# sonar_peripherals.net
KiCad netlist of a schematic drawn in Altium Designer
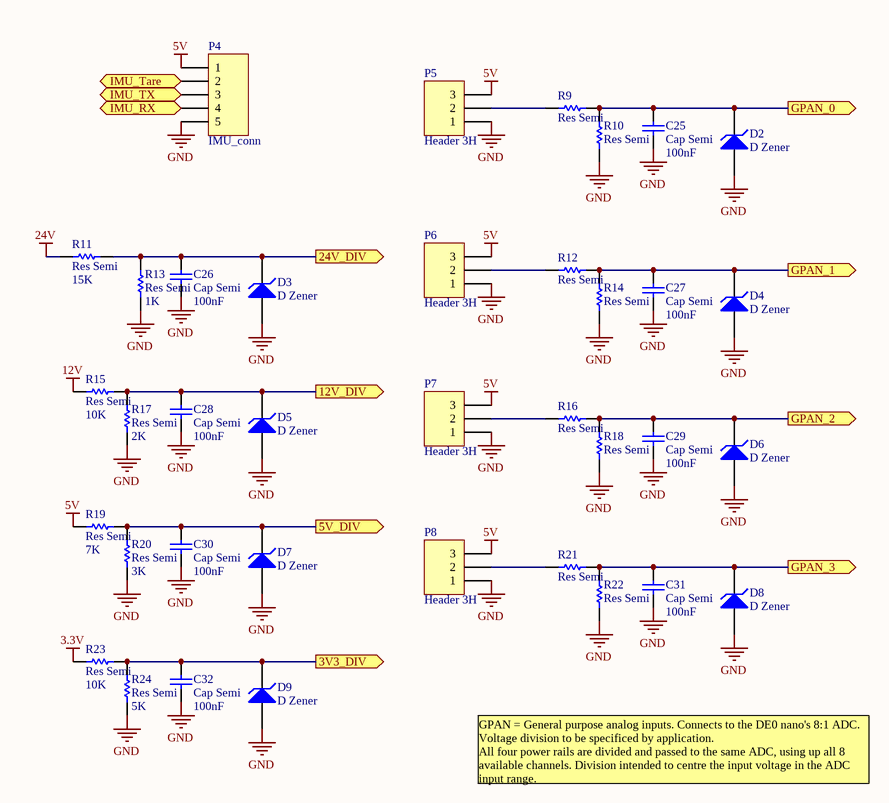
[diagram p0: sonar_peripherals.SchDoc]

(export (version "E")
  (design (tool "Eeschema 10.0.6"))
  (components
    (comp (ref "C25")
      (value "Cap Semi")
      (footprint "C0805")
      (description "Capacitor (Semiconductor SIM Model)")
      (fields (field (name "ALTIUM_VALUE") "100nF") (field (name "PUBLISHER") "Altium Limited"))
      (libsource (lib "Miscellaneous Devices") (part "Cap Semi"))
    )
    (comp (ref "C26")
      (value "Cap Semi")
      (footprint "C0805")
      (description "Capacitor (Semiconductor SIM Model)")
      (fields (field (name "ALTIUM_VALUE") "100nF") (field (name "PUBLISHER") "Altium Limited"))
      (libsource (lib "Miscellaneous Devices") (part "Cap Semi"))
    )
    (comp (ref "C27")
      (value "Cap Semi")
      (footprint "C0805")
      (description "Capacitor (Semiconductor SIM Model)")
      (fields (field (name "ALTIUM_VALUE") "100nF") (field (name "PUBLISHER") "Altium Limited"))
      (libsource (lib "Miscellaneous Devices") (part "Cap Semi"))
    )
    (comp (ref "C28")
      (value "Cap Semi")
      (footprint "C0805")
      (description "Capacitor (Semiconductor SIM Model)")
      (fields (field (name "ALTIUM_VALUE") "100nF") (field (name "PUBLISHER") "Altium Limited"))
      (libsource (lib "Miscellaneous Devices") (part "Cap Semi"))
    )
    (comp (ref "C29")
      (value "Cap Semi")
      (footprint "C0805")
      (description "Capacitor (Semiconductor SIM Model)")
      (fields (field (name "ALTIUM_VALUE") "100nF") (field (name "PUBLISHER") "Altium Limited"))
      (libsource (lib "Miscellaneous Devices") (part "Cap Semi"))
    )
    (comp (ref "C30")
      (value "Cap Semi")
      (footprint "C0805")
      (description "Capacitor (Semiconductor SIM Model)")
      (fields (field (name "ALTIUM_VALUE") "100nF") (field (name "PUBLISHER") "Altium Limited"))
      (libsource (lib "Miscellaneous Devices") (part "Cap Semi"))
    )
    (comp (ref "C31")
      (value "Cap Semi")
      (footprint "C0805")
      (description "Capacitor (Semiconductor SIM Model)")
      (fields (field (name "ALTIUM_VALUE") "100nF") (field (name "PUBLISHER") "Altium Limited"))
      (libsource (lib "Miscellaneous Devices") (part "Cap Semi"))
    )
    (comp (ref "C32")
      (value "Cap Semi")
      (footprint "C0805")
      (description "Capacitor (Semiconductor SIM Model)")
      (fields (field (name "ALTIUM_VALUE") "100nF") (field (name "PUBLISHER") "Altium Limited"))
      (libsource (lib "Miscellaneous Devices") (part "Cap Semi"))
    )
    (comp (ref "D2")
      (value "D Zener")
      (footprint "SOD-323")
      (description "Zener Diode")
      (fields (field (name "PUBLISHER") "Altium Limited"))
      (libsource (lib "Miscellaneous Devices") (part "D Zener"))
    )
    (comp (ref "D3")
      (value "D Zener")
      (footprint "SOD-323")
      (description "Zener Diode")
      (fields (field (name "PUBLISHER") "Altium Limited"))
      (libsource (lib "Miscellaneous Devices") (part "D Zener"))
    )
    (comp (ref "D4")
      (value "D Zener")
      (footprint "SOD-323")
      (description "Zener Diode")
      (fields (field (name "PUBLISHER") "Altium Limited"))
      (libsource (lib "Miscellaneous Devices") (part "D Zener"))
    )
    (comp (ref "D5")
      (value "D Zener")
      (footprint "SOD-323")
      (description "Zener Diode")
      (fields (field (name "PUBLISHER") "Altium Limited"))
      (libsource (lib "Miscellaneous Devices") (part "D Zener"))
    )
    (comp (ref "D6")
      (value "D Zener")
      (footprint "SOD-323")
      (description "Zener Diode")
      (fields (field (name "PUBLISHER") "Altium Limited"))
      (libsource (lib "Miscellaneous Devices") (part "D Zener"))
    )
    (comp (ref "D7")
      (value "D Zener")
      (footprint "SOD-323")
      (description "Zener Diode")
      (fields (field (name "PUBLISHER") "Altium Limited"))
      (libsource (lib "Miscellaneous Devices") (part "D Zener"))
    )
    (comp (ref "D8")
      (value "D Zener")
      (footprint "SOD-323")
      (description "Zener Diode")
      (fields (field (name "PUBLISHER") "Altium Limited"))
      (libsource (lib "Miscellaneous Devices") (part "D Zener"))
    )
    (comp (ref "D9")
      (value "D Zener")
      (footprint "SOD-323")
      (description "Zener Diode")
      (fields (field (name "PUBLISHER") "Altium Limited"))
      (libsource (lib "Miscellaneous Devices") (part "D Zener"))
    )
    (comp (ref "P4")
      (value "IMU_conn")
      (footprint "HDR1X5H")
      (description "Header, 5-Pin, Right Angle")
      (fields (field (name "PUBLISHER") "Altium Limited"))
      (libsource (lib "Miscellaneous Connectors") (part "Header 5H"))
    )
    (comp (ref "P5")
      (value "Header 3H")
      (footprint "HDR1X3H")
      (description "Header, 3-Pin, Right Angle")
      (fields (field (name "PUBLISHER") "Altium Limited"))
      (libsource (lib "Miscellaneous Connectors") (part "Header 3H"))
    )
    (comp (ref "P6")
      (value "Header 3H")
      (footprint "HDR1X3H")
      (description "Header, 3-Pin, Right Angle")
      (fields (field (name "PUBLISHER") "Altium Limited"))
      (libsource (lib "Miscellaneous Connectors") (part "Header 3H"))
    )
    (comp (ref "P7")
      (value "Header 3H")
      (footprint "HDR1X3H")
      (description "Header, 3-Pin, Right Angle")
      (fields (field (name "PUBLISHER") "Altium Limited"))
      (libsource (lib "Miscellaneous Connectors") (part "Header 3H"))
    )
    (comp (ref "P8")
      (value "Header 3H")
      (footprint "HDR1X3H")
      (description "Header, 3-Pin, Right Angle")
      (fields (field (name "PUBLISHER") "Altium Limited"))
      (libsource (lib "Miscellaneous Connectors") (part "Header 3H"))
    )
    (comp (ref "R9")
      (value "Res Semi")
      (footprint "6-0805_M")
      (description "Semiconductor Resistor")
      (fields (field (name "PUBLISHER") "Altium Limited"))
      (libsource (lib "Miscellaneous Devices") (part "Res Semi"))
    )
    (comp (ref "R10")
      (value "Res Semi")
      (footprint "6-0805_M")
      (description "Semiconductor Resistor")
      (fields (field (name "PUBLISHER") "Altium Limited"))
      (libsource (lib "Miscellaneous Devices") (part "Res Semi"))
    )
    (comp (ref "R11")
      (value "Res Semi")
      (footprint "6-0805_M")
      (description "Semiconductor Resistor")
      (fields (field (name "ALTIUM_VALUE") "15K") (field (name "PUBLISHER") "Altium Limited"))
      (libsource (lib "Miscellaneous Devices") (part "Res Semi"))
    )
    (comp (ref "R12")
      (value "Res Semi")
      (footprint "6-0805_M")
      (description "Semiconductor Resistor")
      (fields (field (name "PUBLISHER") "Altium Limited"))
      (libsource (lib "Miscellaneous Devices") (part "Res Semi"))
    )
    (comp (ref "R13")
      (value "Res Semi")
      (footprint "6-0805_M")
      (description "Semiconductor Resistor")
      (fields (field (name "ALTIUM_VALUE") "1K") (field (name "PUBLISHER") "Altium Limited"))
      (libsource (lib "Miscellaneous Devices") (part "Res Semi"))
    )
    (comp (ref "R14")
      (value "Res Semi")
      (footprint "6-0805_M")
      (description "Semiconductor Resistor")
      (fields (field (name "PUBLISHER") "Altium Limited"))
      (libsource (lib "Miscellaneous Devices") (part "Res Semi"))
    )
    (comp (ref "R15")
      (value "Res Semi")
      (footprint "6-0805_M")
      (description "Semiconductor Resistor")
      (fields (field (name "ALTIUM_VALUE") "10K") (field (name "PUBLISHER") "Altium Limited"))
      (libsource (lib "Miscellaneous Devices") (part "Res Semi"))
    )
    (comp (ref "R16")
      (value "Res Semi")
      (footprint "6-0805_M")
      (description "Semiconductor Resistor")
      (fields (field (name "PUBLISHER") "Altium Limited"))
      (libsource (lib "Miscellaneous Devices") (part "Res Semi"))
    )
    (comp (ref "R17")
      (value "Res Semi")
      (footprint "6-0805_M")
      (description "Semiconductor Resistor")
      (fields (field (name "ALTIUM_VALUE") "2K") (field (name "PUBLISHER") "Altium Limited"))
      (libsource (lib "Miscellaneous Devices") (part "Res Semi"))
    )
    (comp (ref "R18")
      (value "Res Semi")
      (footprint "6-0805_M")
      (description "Semiconductor Resistor")
      (fields (field (name "PUBLISHER") "Altium Limited"))
      (libsource (lib "Miscellaneous Devices") (part "Res Semi"))
    )
    (comp (ref "R19")
      (value "Res Semi")
      (footprint "6-0805_M")
      (description "Semiconductor Resistor")
      (fields (field (name "ALTIUM_VALUE") "7K") (field (name "PUBLISHER") "Altium Limited"))
      (libsource (lib "Miscellaneous Devices") (part "Res Semi"))
    )
    (comp (ref "R20")
      (value "Res Semi")
      (footprint "6-0805_M")
      (description "Semiconductor Resistor")
      (fields (field (name "ALTIUM_VALUE") "3K") (field (name "PUBLISHER") "Altium Limited"))
      (libsource (lib "Miscellaneous Devices") (part "Res Semi"))
    )
    (comp (ref "R21")
      (value "Res Semi")
      (footprint "6-0805_M")
      (description "Semiconductor Resistor")
      (fields (field (name "PUBLISHER") "Altium Limited"))
      (libsource (lib "Miscellaneous Devices") (part "Res Semi"))
    )
    (comp (ref "R22")
      (value "Res Semi")
      (footprint "6-0805_M")
      (description "Semiconductor Resistor")
      (fields (field (name "PUBLISHER") "Altium Limited"))
      (libsource (lib "Miscellaneous Devices") (part "Res Semi"))
    )
    (comp (ref "R23")
      (value "Res Semi")
      (footprint "6-0805_M")
      (description "Semiconductor Resistor")
      (fields (field (name "ALTIUM_VALUE") "10K") (field (name "PUBLISHER") "Altium Limited"))
      (libsource (lib "Miscellaneous Devices") (part "Res Semi"))
    )
    (comp (ref "R24")
      (value "Res Semi")
      (footprint "6-0805_M")
      (description "Semiconductor Resistor")
      (fields (field (name "ALTIUM_VALUE") "5K") (field (name "PUBLISHER") "Altium Limited"))
      (libsource (lib "Miscellaneous Devices") (part "Res Semi"))
    )
  )
  (nets
    (net (code "1") (name "/3V3_DIV") (class "Default")
      (node (ref "C32") (pin "2") (pinfunction "2_2") (pintype "passive"))
      (node (ref "D9") (pin "2") (pinfunction "K_2") (pintype "passive"))
      (node (ref "R23") (pin "2") (pinfunction "2_2") (pintype "passive"))
      (node (ref "R24") (pin "2") (pinfunction "2_2") (pintype "passive"))
    )
    (net (code "2") (name "/5V_DIV") (class "Default")
      (node (ref "C30") (pin "2") (pinfunction "2_2") (pintype "passive"))
      (node (ref "D7") (pin "2") (pinfunction "K_2") (pintype "passive"))
      (node (ref "R19") (pin "2") (pinfunction "2_2") (pintype "passive"))
      (node (ref "R20") (pin "2") (pinfunction "2_2") (pintype "passive"))
    )
    (net (code "3") (name "/12V_DIV") (class "Default")
      (node (ref "C28") (pin "2") (pinfunction "2_2") (pintype "passive"))
      (node (ref "D5") (pin "2") (pinfunction "K_2") (pintype "passive"))
      (node (ref "R15") (pin "2") (pinfunction "2_2") (pintype "passive"))
      (node (ref "R17") (pin "2") (pinfunction "2_2") (pintype "passive"))
    )
    (net (code "4") (name "/24V_DIV") (class "Default")
      (node (ref "C26") (pin "2") (pinfunction "2_2") (pintype "passive"))
      (node (ref "D3") (pin "2") (pinfunction "K_2") (pintype "passive"))
      (node (ref "R11") (pin "2") (pinfunction "2_2") (pintype "passive"))
      (node (ref "R13") (pin "2") (pinfunction "2_2") (pintype "passive"))
    )
    (net (code "5") (name "/GPAN_0") (class "Default")
      (node (ref "C25") (pin "2") (pinfunction "2_2") (pintype "passive"))
      (node (ref "D2") (pin "2") (pinfunction "K_2") (pintype "passive"))
      (node (ref "R10") (pin "2") (pinfunction "2_2") (pintype "passive"))
      (node (ref "R9") (pin "2") (pinfunction "2_2") (pintype "passive"))
    )
    (net (code "6") (name "/GPAN_1") (class "Default")
      (node (ref "C27") (pin "2") (pinfunction "2_2") (pintype "passive"))
      (node (ref "D4") (pin "2") (pinfunction "K_2") (pintype "passive"))
      (node (ref "R12") (pin "2") (pinfunction "2_2") (pintype "passive"))
      (node (ref "R14") (pin "2") (pinfunction "2_2") (pintype "passive"))
    )
    (net (code "7") (name "/GPAN_2") (class "Default")
      (node (ref "C29") (pin "2") (pinfunction "2_2") (pintype "passive"))
      (node (ref "D6") (pin "2") (pinfunction "K_2") (pintype "passive"))
      (node (ref "R16") (pin "2") (pinfunction "2_2") (pintype "passive"))
      (node (ref "R18") (pin "2") (pinfunction "2_2") (pintype "passive"))
    )
    (net (code "8") (name "/GPAN_3") (class "Default")
      (node (ref "C31") (pin "2") (pinfunction "2_2") (pintype "passive"))
      (node (ref "D8") (pin "2") (pinfunction "K_2") (pintype "passive"))
      (node (ref "R21") (pin "2") (pinfunction "2_2") (pintype "passive"))
      (node (ref "R22") (pin "2") (pinfunction "2_2") (pintype "passive"))
    )
    (net (code "9") (name "/IMU_RX") (class "Default")
      (node (ref "P4") (pin "4") (pinfunction "4_4") (pintype "passive"))
    )
    (net (code "10") (name "/IMU_TX") (class "Default")
      (node (ref "P4") (pin "3") (pinfunction "3_3") (pintype "passive"))
    )
    (net (code "11") (name "/IMU_Tare") (class "Default")
      (node (ref "P4") (pin "2") (pinfunction "2_2") (pintype "passive"))
    )
    (net (code "12") (name "3.3V") (class "Default")
      (node (ref "R23") (pin "1") (pinfunction "1_1") (pintype "passive"))
    )
    (net (code "13") (name "5V") (class "Default")
      (node (ref "P4") (pin "1") (pinfunction "1_1") (pintype "passive"))
      (node (ref "P5") (pin "3") (pinfunction "3_3") (pintype "passive"))
      (node (ref "P6") (pin "3") (pinfunction "3_3") (pintype "passive"))
      (node (ref "P7") (pin "3") (pinfunction "3_3") (pintype "passive"))
      (node (ref "P8") (pin "3") (pinfunction "3_3") (pintype "passive"))
      (node (ref "R19") (pin "1") (pinfunction "1_1") (pintype "passive"))
    )
    (net (code "14") (name "12V") (class "Default")
      (node (ref "R15") (pin "1") (pinfunction "1_1") (pintype "passive"))
    )
    (net (code "15") (name "24V") (class "Default")
      (node (ref "R11") (pin "1") (pinfunction "1_1") (pintype "passive"))
    )
    (net (code "16") (name "GND") (class "Default")
      (node (ref "C25") (pin "1") (pinfunction "1_1") (pintype "passive"))
      (node (ref "C26") (pin "1") (pinfunction "1_1") (pintype "passive"))
      (node (ref "C27") (pin "1") (pinfunction "1_1") (pintype "passive"))
      (node (ref "C28") (pin "1") (pinfunction "1_1") (pintype "passive"))
      (node (ref "C29") (pin "1") (pinfunction "1_1") (pintype "passive"))
      (node (ref "C30") (pin "1") (pinfunction "1_1") (pintype "passive"))
      (node (ref "C31") (pin "1") (pinfunction "1_1") (pintype "passive"))
      (node (ref "C32") (pin "1") (pinfunction "1_1") (pintype "passive"))
      (node (ref "D2") (pin "1") (pinfunction "A_1") (pintype "passive"))
      (node (ref "D3") (pin "1") (pinfunction "A_1") (pintype "passive"))
      (node (ref "D4") (pin "1") (pinfunction "A_1") (pintype "passive"))
      (node (ref "D5") (pin "1") (pinfunction "A_1") (pintype "passive"))
      (node (ref "D6") (pin "1") (pinfunction "A_1") (pintype "passive"))
      (node (ref "D7") (pin "1") (pinfunction "A_1") (pintype "passive"))
      (node (ref "D8") (pin "1") (pinfunction "A_1") (pintype "passive"))
      (node (ref "D9") (pin "1") (pinfunction "A_1") (pintype "passive"))
      (node (ref "P4") (pin "5") (pinfunction "5_5") (pintype "passive"))
      (node (ref "P5") (pin "1") (pinfunction "1_1") (pintype "passive"))
      (node (ref "P6") (pin "1") (pinfunction "1_1") (pintype "passive"))
      (node (ref "P7") (pin "1") (pinfunction "1_1") (pintype "passive"))
      (node (ref "P8") (pin "1") (pinfunction "1_1") (pintype "passive"))
      (node (ref "R10") (pin "1") (pinfunction "1_1") (pintype "passive"))
      (node (ref "R13") (pin "1") (pinfunction "1_1") (pintype "passive"))
      (node (ref "R14") (pin "1") (pinfunction "1_1") (pintype "passive"))
      (node (ref "R17") (pin "1") (pinfunction "1_1") (pintype "passive"))
      (node (ref "R18") (pin "1") (pinfunction "1_1") (pintype "passive"))
      (node (ref "R20") (pin "1") (pinfunction "1_1") (pintype "passive"))
      (node (ref "R22") (pin "1") (pinfunction "1_1") (pintype "passive"))
      (node (ref "R24") (pin "1") (pinfunction "1_1") (pintype "passive"))
    )
    (net (code "17") (name "Net-(P5-Pad2)") (class "Default")
      (node (ref "P5") (pin "2") (pinfunction "2_2") (pintype "passive"))
      (node (ref "R9") (pin "1") (pinfunction "1_1") (pintype "passive"))
    )
    (net (code "18") (name "Net-(P6-Pad2)") (class "Default")
      (node (ref "P6") (pin "2") (pinfunction "2_2") (pintype "passive"))
      (node (ref "R12") (pin "1") (pinfunction "1_1") (pintype "passive"))
    )
    (net (code "19") (name "Net-(P7-Pad2)") (class "Default")
      (node (ref "P7") (pin "2") (pinfunction "2_2") (pintype "passive"))
      (node (ref "R16") (pin "1") (pinfunction "1_1") (pintype "passive"))
    )
    (net (code "20") (name "Net-(P8-Pad2)") (class "Default")
      (node (ref "P8") (pin "2") (pinfunction "2_2") (pintype "passive"))
      (node (ref "R21") (pin "1") (pinfunction "1_1") (pintype "passive"))
    )
  )
)
